# MCU_32.net
KiCad netlist of a schematic drawn in Altium Designer
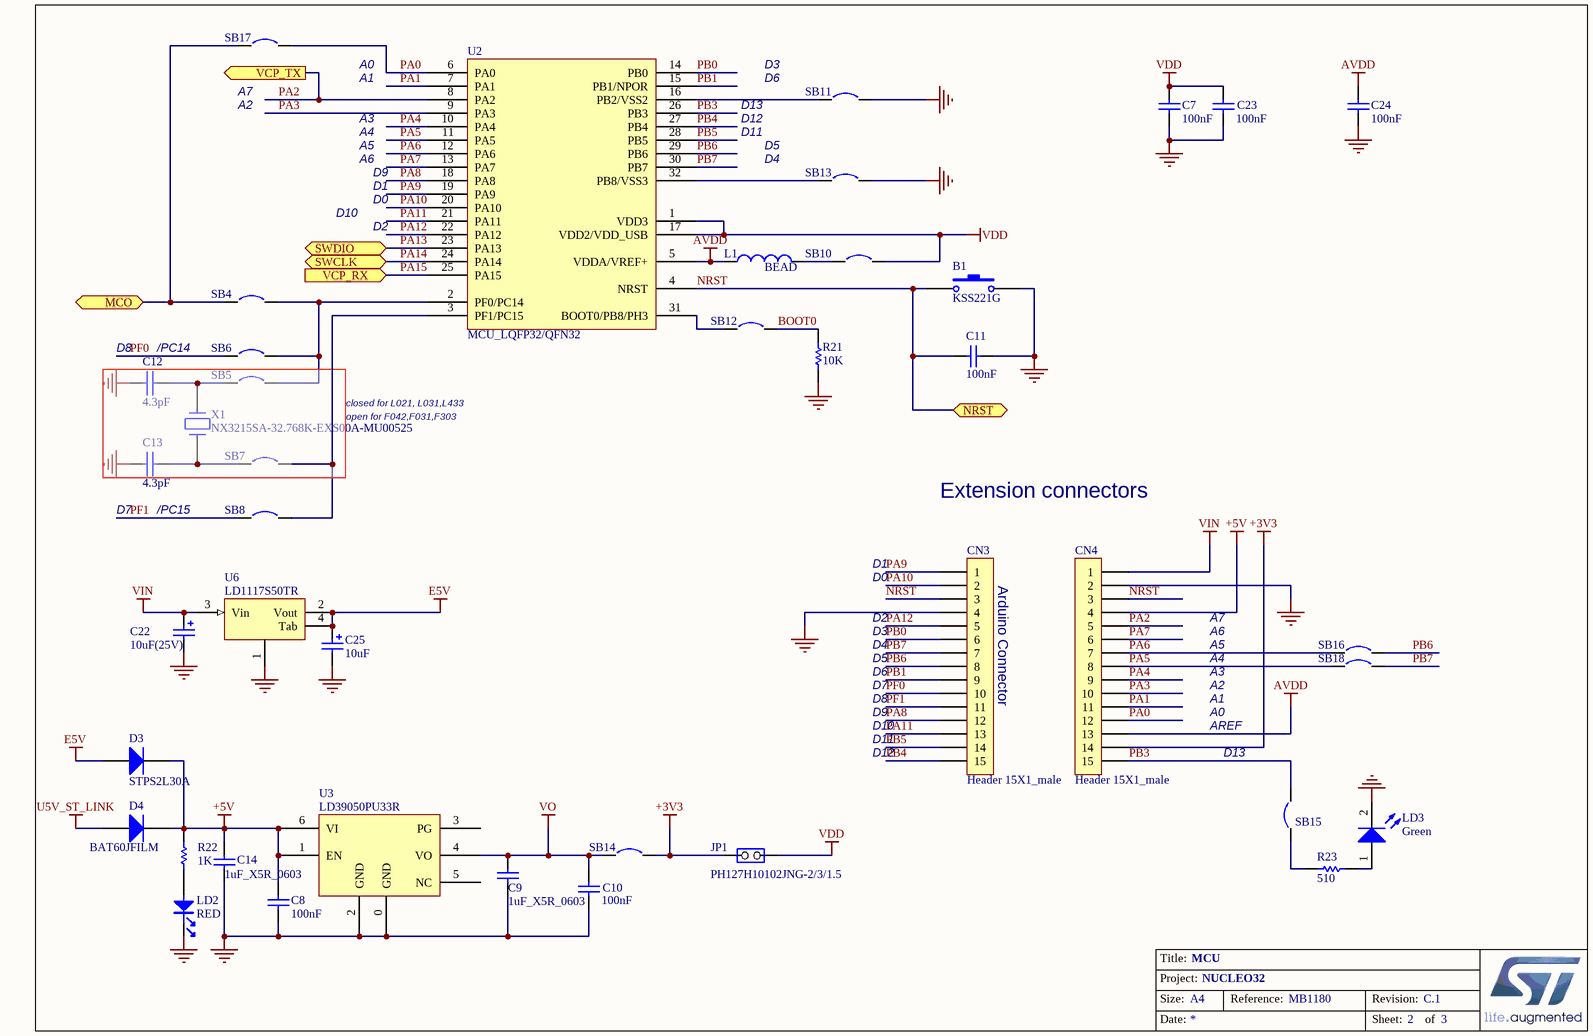
[diagram p0: MCU_32.SchDoc]

(export (version "E")
  (design (tool "Eeschema 10.0.6"))
  (components
    (comp (ref "B1")
      (value "KSS221G")
      (footprint "SW2_5R6_5R5x3R1")
      (description "Switch")
      (fields (field (name "PUBLISHER") "Altium Limited"))
      (libsource (lib "Miscellaneous Devices") (part "SW-PB"))
    )
    (comp (ref "C7")
      (value "100nF")
      (footprint "0603C")
      (description "Capacitor")
      (fields (field (name "PUBLISHER") "Altium Limited"))
      (libsource (lib "Miscellaneous Devices") (part "Cap"))
    )
    (comp (ref "C8")
      (value "100nF")
      (footprint "0603C")
      (description "Capacitor 0402 / 0603 / 0805")
      (libsource (lib "MCD_TOOLS") (part "Capacitor_ST"))
    )
    (comp (ref "C9")
      (value "1uF_X5R_0603")
      (footprint "0603C")
      (description "0603  X5R 1µF")
      (fields (field (name "TOLERANCE") "10%"))
      (libsource (lib "MB963_1") (part "CAP SMD 0603  X5R 1µF 25V 10%"))
    )
    (comp (ref "C10")
      (value "100nF")
      (footprint "0603C")
      (description "Capacitor 0402 / 0603 / 0805")
      (libsource (lib "MCD_TOOLS") (part "Capacitor_ST"))
    )
    (comp (ref "C11")
      (value "100nF")
      (footprint "0603C")
      (description "Capacitor")
      (fields (field (name "PUBLISHER") "Altium Limited"))
      (libsource (lib "Miscellaneous Devices") (part "CAP"))
    )
    (comp (ref "C12")
      (value "4.3pF")
      (footprint "0603C")
      (description "Capacitor")
      (libsource (lib "*") (part "CAP"))
    )
    (comp (ref "C13")
      (value "4.3pF")
      (footprint "0603C")
      (description "Capacitor")
      (libsource (lib "*") (part "CAP"))
    )
    (comp (ref "C14")
      (value "1uF_X5R_0603")
      (footprint "0603C")
      (description "0603  X5R 1µF")
      (fields (field (name "TOLERANCE") "10%"))
      (libsource (lib "MB963_1") (part "CAP SMD 0603  X5R 1µF 25V 10%"))
    )
    (comp (ref "C22")
      (value "10uF(25V)")
      (footprint "TAN_B")
      (description "Polarized Capacitor (Radial)")
      (fields (field (name "PUBLISHER") "Altium Limited"))
      (libsource (lib "Miscellaneous Devices") (part "Cap Pol1"))
    )
    (comp (ref "C23")
      (value "100nF")
      (footprint "0603C")
      (description "Capacitor")
      (fields (field (name "PUBLISHER") "Altium Limited"))
      (libsource (lib "Miscellaneous Devices") (part "Cap"))
    )
    (comp (ref "C24")
      (value "100nF")
      (footprint "0603C")
      (description "Capacitor")
      (fields (field (name "PUBLISHER") "Altium Limited"))
      (libsource (lib "Miscellaneous Devices") (part "Cap"))
    )
    (comp (ref "C25")
      (value "10uF")
      (footprint "TAN_A")
      (description "Polarized Capacitor (Radial)")
      (fields (field (name "PUBLISHER") "Altium Limited"))
      (libsource (lib "Miscellaneous Devices") (part "Cap Pol1"))
    )
    (comp (ref "CN3")
      (value "Header 15X1_male")
      (footprint "HDR_1x15_2R54_V_F")
      (description "Header, 10-Pin, Single row,female")
      (fields (field (name "PUBLISHER") "Altium Limited"))
      (libsource (lib "") (part "Header 15X1_Female_1_1"))
    )
    (comp (ref "CN4")
      (value "Header 15X1_male")
      (footprint "HDR_1x15_2R54_V_F")
      (description "Header, 10-Pin, Single row,female")
      (fields (field (name "PUBLISHER") "Altium Limited"))
      (libsource (lib "MB1180") (part "Header 15X1_Female_1"))
    )
    (comp (ref "D3") (value "STPS2L30A") (footprint "SMA") (libsource (lib "Nucleo_64") (part "STPS2L30A")))
    (comp (ref "D4")
      (value "BAT60JFILM")
      (footprint "SOD-323")
      (libsource (lib "MCD_TOOLS") (part "BAT60JFILM"))
    )
    (comp (ref "JP1")
      (value "PH127H10102JNG-2/3/1.5")
      (footprint "HDR_1x2_1R27_R_M")
      (libsource (lib "*") (part "JP2"))
    )
    (comp (ref "L1")
      (value "BEAD")
      (footprint "0603L")
      (description "Inductor")
      (fields (field (name "PUBLISHER") "Altium Limited"))
      (libsource (lib "Miscellaneous Devices") (part "Inductor"))
    )
    (comp (ref "LD2") (value "RED") (footprint "0603D_R") (libsource (lib "MB963_1") (part "PHOTO")))
    (comp (ref "LD3")
      (value "Green")
      (footprint "0603D_G")
      (description "Typical RED, GREEN, YELLOW, AMBER GaAs LED")
      (fields (field (name "PUBLISHER") "Altium Limited"))
      (libsource (lib "Miscellaneous Devices") (part "LED2"))
    )
    (comp (ref "R21")
      (value "10K")
      (footprint "0603R")
      (description "Resistor")
      (fields (field (name "PUBLISHER") "Altium Limited"))
      (libsource (lib "Miscellaneous Devices") (part "res1"))
    )
    (comp (ref "R22")
      (value "1K")
      (footprint "0603R")
      (description "Resistor 0402 or 0603 or 0805")
      (libsource (lib "MCD_TOOLS") (part "Resistor_ST"))
    )
    (comp (ref "R23")
      (value "510")
      (footprint "0603R")
      (description "Resistor")
      (fields (field (name "PUBLISHER") "Altium Limited"))
      (libsource (lib "Miscellaneous Devices") (part "Res1"))
    )
    (comp (ref "SB4")
      (value "Circuit Breaker (open)")
      (footprint "SB_0603")
      (description "Circuit Breaker")
      (fields (field (name "PUBLISHER") "Altium Limited"))
      (libsource (lib "MCD_TOOLS") (part "Circuit Breaker"))
    )
    (comp (ref "SB5")
      (value "Circuit Breaker")
      (footprint "SB_0603")
      (fields (field (name "PUBLISHER") "Altium Limited"))
      (libsource (lib "MCD_TOOLS") (part "Circuit Breaker"))
    )
    (comp (ref "SB6")
      (value "Circuit Breaker")
      (footprint "SB_0603")
      (fields (field (name "PUBLISHER") "Altium Limited"))
      (libsource (lib "MCD_TOOLS") (part "Circuit Breaker"))
    )
    (comp (ref "SB7")
      (value "Circuit Breaker")
      (footprint "SB_0603")
      (fields (field (name "PUBLISHER") "Altium Limited"))
      (libsource (lib "MCD_TOOLS") (part "Circuit Breaker"))
    )
    (comp (ref "SB8")
      (value "Circuit Breaker")
      (footprint "SB_0603")
      (fields (field (name "PUBLISHER") "Altium Limited"))
      (libsource (lib "MCD_TOOLS") (part "Circuit Breaker"))
    )
    (comp (ref "SB10")
      (value "Circuit Breaker (close)")
      (footprint "SB_0603")
      (description "Circuit Breaker")
      (fields (field (name "PUBLISHER") "Altium Limited"))
      (libsource (lib "MCD_TOOLS") (part "Circuit Breaker"))
    )
    (comp (ref "SB11")
      (value "Circuit Breaker (close)")
      (footprint "SB_0603")
      (description "Circuit Breaker")
      (fields (field (name "PUBLISHER") "Altium Limited"))
      (libsource (lib "MCD_TOOLS") (part "Circuit Breaker"))
    )
    (comp (ref "SB12")
      (value "Circuit Breaker (close)")
      (footprint "SB_0603")
      (description "Circuit Breaker")
      (fields (field (name "PUBLISHER") "Altium Limited"))
      (libsource (lib "MCD_TOOLS") (part "Circuit Breaker"))
    )
    (comp (ref "SB13")
      (value "Circuit Breaker (close)")
      (footprint "SB_0603")
      (description "Circuit Breaker")
      (fields (field (name "PUBLISHER") "Altium Limited"))
      (libsource (lib "MCD_TOOLS") (part "Circuit Breaker"))
    )
    (comp (ref "SB14")
      (value "Circuit Breaker (close)")
      (footprint "SB_0603")
      (description "Circuit Breaker")
      (fields (field (name "PUBLISHER") "Altium Limited"))
      (libsource (lib "MCD_TOOLS") (part "Circuit Breaker"))
    )
    (comp (ref "SB15")
      (value "Circuit Breaker (close)")
      (footprint "SB_0603")
      (description "Circuit Breaker")
      (fields (field (name "PUBLISHER") "Altium Limited"))
      (libsource (lib "MCD_TOOLS") (part "Circuit Breaker"))
    )
    (comp (ref "SB16")
      (value "Circuit Breaker (close)")
      (footprint "SB_0603")
      (description "Circuit Breaker")
      (fields (field (name "PUBLISHER") "Altium Limited"))
      (libsource (lib "MCD_TOOLS") (part "Circuit Breaker"))
    )
    (comp (ref "SB17")
      (value "Circuit Breaker (open)")
      (footprint "SB_0603")
      (description "Circuit Breaker")
      (fields (field (name "PUBLISHER") "Altium Limited"))
      (libsource (lib "MCD_TOOLS") (part "Circuit Breaker"))
    )
    (comp (ref "SB18")
      (value "Circuit Breaker (close)")
      (footprint "SB_0603")
      (description "Circuit Breaker")
      (fields (field (name "PUBLISHER") "Altium Limited"))
      (libsource (lib "MCD_TOOLS") (part "Circuit Breaker"))
    )
    (comp (ref "U2")
      (value "MCU_LQFP32/QFN32")
      (footprint "LQFP32_0R5_7x7")
      (libsource (lib "MB1180") (part "MCU_LQFP32"))
    )
    (comp (ref "U3")
      (value "LD39050PU33R")
      (footprint "DFN6_0R95_3x3_TP")
      (libsource (lib "MB1180") (part "LD39050P"))
    )
    (comp (ref "U6") (value "LD1117S50TR") (footprint "SOT-223") (libsource (lib "MB1180") (part "LD1117")))
    (comp (ref "X1")
      (value "NX3215SA-32.768K-EXS00A-MU00525")
      (footprint "XTAL_2SM_3R2X1R5")
      (description "Crystal")
      (libsource (lib "MB1167") (part "CRYSTAL_32K"))
    )
  )
  (nets
    (net (code "1") (name "+3V3") (class "Default")
      (node (ref "CN4") (pin "14") (pinfunction "14_14") (pintype "passive"))
      (node (ref "JP1") (pin "1") (pinfunction "COMMON_1") (pintype "passive"))
      (node (ref "SB14") (pin "2") (pinfunction "2_2") (pintype "passive"))
    )
    (net (code "2") (name "+5V") (class "Default")
      (node (ref "C14") (pin "1") (pinfunction "1_1") (pintype "passive"))
      (node (ref "C8") (pin "2") (pinfunction "2_2") (pintype "passive"))
      (node (ref "CN4") (pin "4") (pinfunction "4_4") (pintype "passive"))
      (node (ref "D3") (pin "2") (pinfunction "K_2") (pintype "passive"))
      (node (ref "D4") (pin "2") (pinfunction "K_2") (pintype "passive"))
      (node (ref "R22") (pin "2") (pinfunction "2_2") (pintype "passive"))
      (node (ref "U3") (pin "1") (pinfunction "EN_1") (pintype "passive"))
      (node (ref "U3") (pin "6") (pinfunction "VI_6") (pintype "passive"))
    )
    (net (code "3") (name "/BOOT0") (class "Default")
      (node (ref "R21") (pin "1") (pinfunction "1_1") (pintype "passive"))
      (node (ref "SB12") (pin "2") (pinfunction "2_2") (pintype "passive"))
    )
    (net (code "4") (name "/MCO") (class "Default")
      (node (ref "SB17") (pin "1") (pinfunction "1_1") (pintype "passive"))
      (node (ref "SB4") (pin "1") (pinfunction "1_1") (pintype "passive"))
    )
    (net (code "5") (name "/NRST") (class "Default")
      (node (ref "B1") (pin "1") (pinfunction "1_1") (pintype "passive"))
      (node (ref "C11") (pin "2") (pinfunction "2_2") (pintype "passive"))
      (node (ref "CN3") (pin "3") (pinfunction "3_3") (pintype "passive"))
      (node (ref "CN4") (pin "3") (pinfunction "3_3") (pintype "passive"))
      (node (ref "U2") (pin "4") (pinfunction "NRST_4") (pintype "passive"))
    )
    (net (code "6") (name "/PA0") (class "Default")
      (node (ref "CN4") (pin "12") (pinfunction "12_12") (pintype "passive"))
      (node (ref "SB17") (pin "2") (pinfunction "2_2") (pintype "passive"))
      (node (ref "U2") (pin "6") (pinfunction "PA0_6") (pintype "passive"))
    )
    (net (code "7") (name "/PA1") (class "Default")
      (node (ref "CN4") (pin "11") (pinfunction "11_11") (pintype "passive"))
      (node (ref "U2") (pin "7") (pinfunction "PA1_7") (pintype "passive"))
    )
    (net (code "8") (name "/PA2") (class "Default")
      (node (ref "CN4") (pin "5") (pinfunction "5_5") (pintype "passive"))
      (node (ref "U2") (pin "8") (pinfunction "PA2_8") (pintype "passive"))
    )
    (net (code "9") (name "/PA3") (class "Default")
      (node (ref "CN4") (pin "10") (pinfunction "10_10") (pintype "passive"))
      (node (ref "U2") (pin "9") (pinfunction "PA3_9") (pintype "passive"))
    )
    (net (code "10") (name "/PA4") (class "Default")
      (node (ref "CN4") (pin "9") (pinfunction "9_9") (pintype "passive"))
      (node (ref "U2") (pin "10") (pinfunction "PA4_10") (pintype "passive"))
    )
    (net (code "11") (name "/PA5") (class "Default")
      (node (ref "CN4") (pin "8") (pinfunction "8_8") (pintype "passive"))
      (node (ref "SB18") (pin "1") (pinfunction "1_1") (pintype "passive"))
      (node (ref "U2") (pin "11") (pinfunction "PA5_11") (pintype "passive"))
    )
    (net (code "12") (name "/PA6") (class "Default")
      (node (ref "CN4") (pin "7") (pinfunction "7_7") (pintype "passive"))
      (node (ref "SB16") (pin "1") (pinfunction "1_1") (pintype "passive"))
      (node (ref "U2") (pin "12") (pinfunction "PA6_12") (pintype "passive"))
    )
    (net (code "13") (name "/PA7") (class "Default")
      (node (ref "CN4") (pin "6") (pinfunction "6_6") (pintype "passive"))
      (node (ref "U2") (pin "13") (pinfunction "PA7_13") (pintype "passive"))
    )
    (net (code "14") (name "/PA8") (class "Default")
      (node (ref "CN3") (pin "12") (pinfunction "12_12") (pintype "passive"))
      (node (ref "U2") (pin "18") (pinfunction "PA8_18") (pintype "passive"))
    )
    (net (code "15") (name "/PA9") (class "Default")
      (node (ref "CN3") (pin "1") (pinfunction "1_1") (pintype "passive"))
      (node (ref "U2") (pin "19") (pinfunction "PA9_19") (pintype "passive"))
    )
    (net (code "16") (name "/PA10") (class "Default")
      (node (ref "CN3") (pin "2") (pinfunction "2_2") (pintype "passive"))
      (node (ref "U2") (pin "20") (pinfunction "PA10_20") (pintype "passive"))
    )
    (net (code "17") (name "/PA11") (class "Default")
      (node (ref "CN3") (pin "13") (pinfunction "13_13") (pintype "passive"))
      (node (ref "U2") (pin "21") (pinfunction "PA11_21") (pintype "passive"))
    )
    (net (code "18") (name "/PA12") (class "Default")
      (node (ref "CN3") (pin "5") (pinfunction "5_5") (pintype "passive"))
      (node (ref "U2") (pin "22") (pinfunction "PA12_22") (pintype "passive"))
    )
    (net (code "19") (name "/PA13") (class "Default")
      (node (ref "U2") (pin "23") (pinfunction "PA13_23") (pintype "passive"))
    )
    (net (code "20") (name "/PA14") (class "Default")
      (node (ref "U2") (pin "24") (pinfunction "PA14_24") (pintype "passive"))
    )
    (net (code "21") (name "/PA15") (class "Default")
      (node (ref "U2") (pin "25") (pinfunction "PA15_25") (pintype "passive"))
    )
    (net (code "22") (name "/PB0") (class "Default")
      (node (ref "CN3") (pin "6") (pinfunction "6_6") (pintype "passive"))
      (node (ref "U2") (pin "14") (pinfunction "PB0_14") (pintype "passive"))
    )
    (net (code "23") (name "/PB1") (class "Default")
      (node (ref "CN3") (pin "9") (pinfunction "9_9") (pintype "passive"))
      (node (ref "U2") (pin "15") (pinfunction "PB1/NPOR_15") (pintype "passive"))
    )
    (net (code "24") (name "/PB3") (class "Default")
      (node (ref "CN4") (pin "15") (pinfunction "15_15") (pintype "passive"))
      (node (ref "SB15") (pin "2") (pinfunction "2_2") (pintype "passive"))
      (node (ref "U2") (pin "26") (pinfunction "PB3_26") (pintype "passive"))
    )
    (net (code "25") (name "/PB4") (class "Default")
      (node (ref "CN3") (pin "15") (pinfunction "15_15") (pintype "passive"))
      (node (ref "U2") (pin "27") (pinfunction "PB4_27") (pintype "passive"))
    )
    (net (code "26") (name "/PB5") (class "Default")
      (node (ref "CN3") (pin "14") (pinfunction "14_14") (pintype "passive"))
      (node (ref "U2") (pin "28") (pinfunction "PB5_28") (pintype "passive"))
    )
    (net (code "27") (name "/PB6") (class "Default")
      (node (ref "CN3") (pin "8") (pinfunction "8_8") (pintype "passive"))
      (node (ref "SB16") (pin "2") (pinfunction "2_2") (pintype "passive"))
      (node (ref "U2") (pin "29") (pinfunction "PB6_29") (pintype "passive"))
    )
    (net (code "28") (name "/PB7") (class "Default")
      (node (ref "CN3") (pin "7") (pinfunction "7_7") (pintype "passive"))
      (node (ref "SB18") (pin "2") (pinfunction "2_2") (pintype "passive"))
      (node (ref "U2") (pin "30") (pinfunction "PB7_30") (pintype "passive"))
    )
    (net (code "29") (name "/PF0") (class "Default")
      (node (ref "CN3") (pin "10") (pinfunction "10_10") (pintype "passive"))
      (node (ref "SB6") (pin "1") (pinfunction "1_1") (pintype "passive"))
    )
    (net (code "30") (name "/PF1") (class "Default")
      (node (ref "CN3") (pin "11") (pinfunction "11_11") (pintype "passive"))
      (node (ref "SB8") (pin "1") (pinfunction "1_1") (pintype "passive"))
    )
    (net (code "31") (name "AVDD") (class "Default")
      (node (ref "C24") (pin "1") (pinfunction "1_1") (pintype "passive"))
      (node (ref "CN4") (pin "13") (pinfunction "13_13") (pintype "passive"))
      (node (ref "L1") (pin "1") (pinfunction "1_1") (pintype "passive"))
      (node (ref "U2") (pin "5") (pinfunction "VDDA/VREF+_5") (pintype "passive"))
    )
    (net (code "32") (name "E5V") (class "Default")
      (node (ref "C25") (pin "1") (pinfunction "1_1") (pintype "passive"))
      (node (ref "D3") (pin "1") (pinfunction "A_1") (pintype "passive"))
      (node (ref "U6") (pin "2") (pinfunction "Vout_2") (pintype "power_in"))
      (node (ref "U6") (pin "4") (pinfunction "Tab_4") (pintype "power_in"))
    )
    (net (code "33") (name "GND") (class "Default")
      (node (ref "B1") (pin "2") (pinfunction "2_2") (pintype "passive"))
      (node (ref "C10") (pin "1") (pinfunction "1_1") (pintype "passive"))
      (node (ref "C11") (pin "1") (pinfunction "1_1") (pintype "passive"))
      (node (ref "C12") (pin "2") (pinfunction "2_2") (pintype "passive"))
      (node (ref "C13") (pin "2") (pinfunction "2_2") (pintype "passive"))
      (node (ref "C14") (pin "2") (pinfunction "2_2") (pintype "passive"))
      (node (ref "C22") (pin "2") (pinfunction "2_2") (pintype "passive"))
      (node (ref "C23") (pin "2") (pinfunction "2_2") (pintype "passive"))
      (node (ref "C24") (pin "2") (pinfunction "2_2") (pintype "passive"))
      (node (ref "C25") (pin "2") (pinfunction "2_2") (pintype "passive"))
      (node (ref "C7") (pin "2") (pinfunction "2_2") (pintype "passive"))
      (node (ref "C8") (pin "1") (pinfunction "1_1") (pintype "passive"))
      (node (ref "C9") (pin "2") (pinfunction "2_2") (pintype "passive"))
      (node (ref "CN3") (pin "4") (pinfunction "4_4") (pintype "passive"))
      (node (ref "CN4") (pin "2") (pinfunction "2_2") (pintype "passive"))
      (node (ref "LD2") (pin "2") (pintype "passive"))
      (node (ref "LD3") (pin "2") (pinfunction "K_2") (pintype "passive"))
      (node (ref "R21") (pin "2") (pinfunction "2_2") (pintype "passive"))
      (node (ref "SB11") (pin "2") (pinfunction "2_2") (pintype "passive"))
      (node (ref "SB13") (pin "2") (pinfunction "2_2") (pintype "passive"))
      (node (ref "U3") (pin "0") (pinfunction "GND_0") (pintype "passive"))
      (node (ref "U3") (pin "2") (pinfunction "GND_2") (pintype "passive"))
      (node (ref "U6") (pin "1") (pintype "passive"))
    )
    (net (code "34") (name "Net-(C12-Pad1)") (class "Default")
      (node (ref "C12") (pin "1") (pinfunction "1_1") (pintype "passive"))
      (node (ref "SB5") (pin "1") (pinfunction "1_1") (pintype "passive"))
      (node (ref "X1") (pin "1") (pinfunction "1_1") (pintype "passive"))
    )
    (net (code "35") (name "Net-(C13-Pad1)") (class "Default")
      (node (ref "C13") (pin "1") (pinfunction "1_1") (pintype "passive"))
      (node (ref "SB7") (pin "1") (pinfunction "1_1") (pintype "passive"))
      (node (ref "X1") (pin "2") (pinfunction "2_2") (pintype "passive"))
    )
    (net (code "36") (name "Net-(L1-Pad2)") (class "Default")
      (node (ref "L1") (pin "2") (pinfunction "2_2") (pintype "passive"))
      (node (ref "SB10") (pin "1") (pinfunction "1_1") (pintype "passive"))
    )
    (net (code "37") (name "Net-(LD2-Pad1)") (class "Default")
      (node (ref "LD2") (pin "1") (pintype "passive"))
      (node (ref "R22") (pin "1") (pinfunction "1_1") (pintype "passive"))
    )
    (net (code "38") (name "Net-(LD3-A)") (class "Default")
      (node (ref "LD3") (pin "1") (pinfunction "A_1") (pintype "passive"))
      (node (ref "R23") (pin "1") (pinfunction "1_1") (pintype "passive"))
    )
    (net (code "39") (name "Net-(R23-Pad2)") (class "Default")
      (node (ref "R23") (pin "2") (pinfunction "2_2") (pintype "passive"))
      (node (ref "SB15") (pin "1") (pinfunction "1_1") (pintype "passive"))
    )
    (net (code "40") (name "Net-(U2-BOOT0{slash}PB8{slash}PH3)") (class "Default")
      (node (ref "SB12") (pin "1") (pinfunction "1_1") (pintype "passive"))
      (node (ref "U2") (pin "31") (pinfunction "BOOT0/PB8/PH3_31") (pintype "passive"))
    )
    (net (code "41") (name "Net-(U2-PB2{slash}VSS2)") (class "Default")
      (node (ref "SB11") (pin "1") (pinfunction "1_1") (pintype "passive"))
      (node (ref "U2") (pin "16") (pinfunction "PB2/VSS2_16") (pintype "passive"))
    )
    (net (code "42") (name "Net-(U2-PB8{slash}VSS3)") (class "Default")
      (node (ref "SB13") (pin "1") (pinfunction "1_1") (pintype "passive"))
      (node (ref "U2") (pin "32") (pinfunction "PB8/VSS3_32") (pintype "passive"))
    )
    (net (code "43") (name "Net-(U2-PF0{slash}PC14)") (class "Default")
      (node (ref "SB4") (pin "2") (pinfunction "2_2") (pintype "passive"))
      (node (ref "SB5") (pin "2") (pinfunction "2_2") (pintype "passive"))
      (node (ref "SB6") (pin "2") (pinfunction "2_2") (pintype "passive"))
      (node (ref "U2") (pin "2") (pinfunction "PF0/PC14_2") (pintype "passive"))
    )
    (net (code "44") (name "Net-(U2-PF1{slash}PC15)") (class "Default")
      (node (ref "SB7") (pin "2") (pinfunction "2_2") (pintype "passive"))
      (node (ref "SB8") (pin "2") (pinfunction "2_2") (pintype "passive"))
      (node (ref "U2") (pin "3") (pinfunction "PF1/PC15_3") (pintype "passive"))
    )
    (net (code "45") (name "U5V_ST_LINK") (class "Default")
      (node (ref "D4") (pin "1") (pinfunction "A_1") (pintype "passive"))
    )
    (net (code "46") (name "VDD") (class "Default")
      (node (ref "C23") (pin "1") (pinfunction "1_1") (pintype "passive"))
      (node (ref "C7") (pin "1") (pinfunction "1_1") (pintype "passive"))
      (node (ref "JP1") (pin "2") (pinfunction "NO_2") (pintype "passive"))
      (node (ref "SB10") (pin "2") (pinfunction "2_2") (pintype "passive"))
      (node (ref "U2") (pin "1") (pinfunction "VDD3_1") (pintype "passive"))
      (node (ref "U2") (pin "17") (pinfunction "VDD2/VDD_USB_17") (pintype "passive"))
    )
    (net (code "47") (name "VIN") (class "Default")
      (node (ref "C22") (pin "1") (pinfunction "1_1") (pintype "passive"))
      (node (ref "CN4") (pin "1") (pinfunction "1_1") (pintype "passive"))
      (node (ref "U6") (pin "3") (pinfunction "Vin_3") (pintype "input"))
    )
    (net (code "48") (name "VO") (class "Default")
      (node (ref "C10") (pin "2") (pinfunction "2_2") (pintype "passive"))
      (node (ref "C9") (pin "1") (pinfunction "1_1") (pintype "passive"))
      (node (ref "SB14") (pin "1") (pinfunction "1_1") (pintype "passive"))
      (node (ref "U3") (pin "4") (pinfunction "VO_4") (pintype "passive"))
    )
    (net (code "49") (name "unconnected-(U3-NC-Pad5)") (class "Default")
      (node (ref "U3") (pin "5") (pinfunction "NC_5") (pintype "passive"))
    )
    (net (code "50") (name "unconnected-(U3-PG-Pad3)") (class "Default")
      (node (ref "U3") (pin "3") (pinfunction "PG_3") (pintype "passive"))
    )
  )
)
